# atsams70n-switch.net
KiCad netlist of a schematic drawn in EAGLE
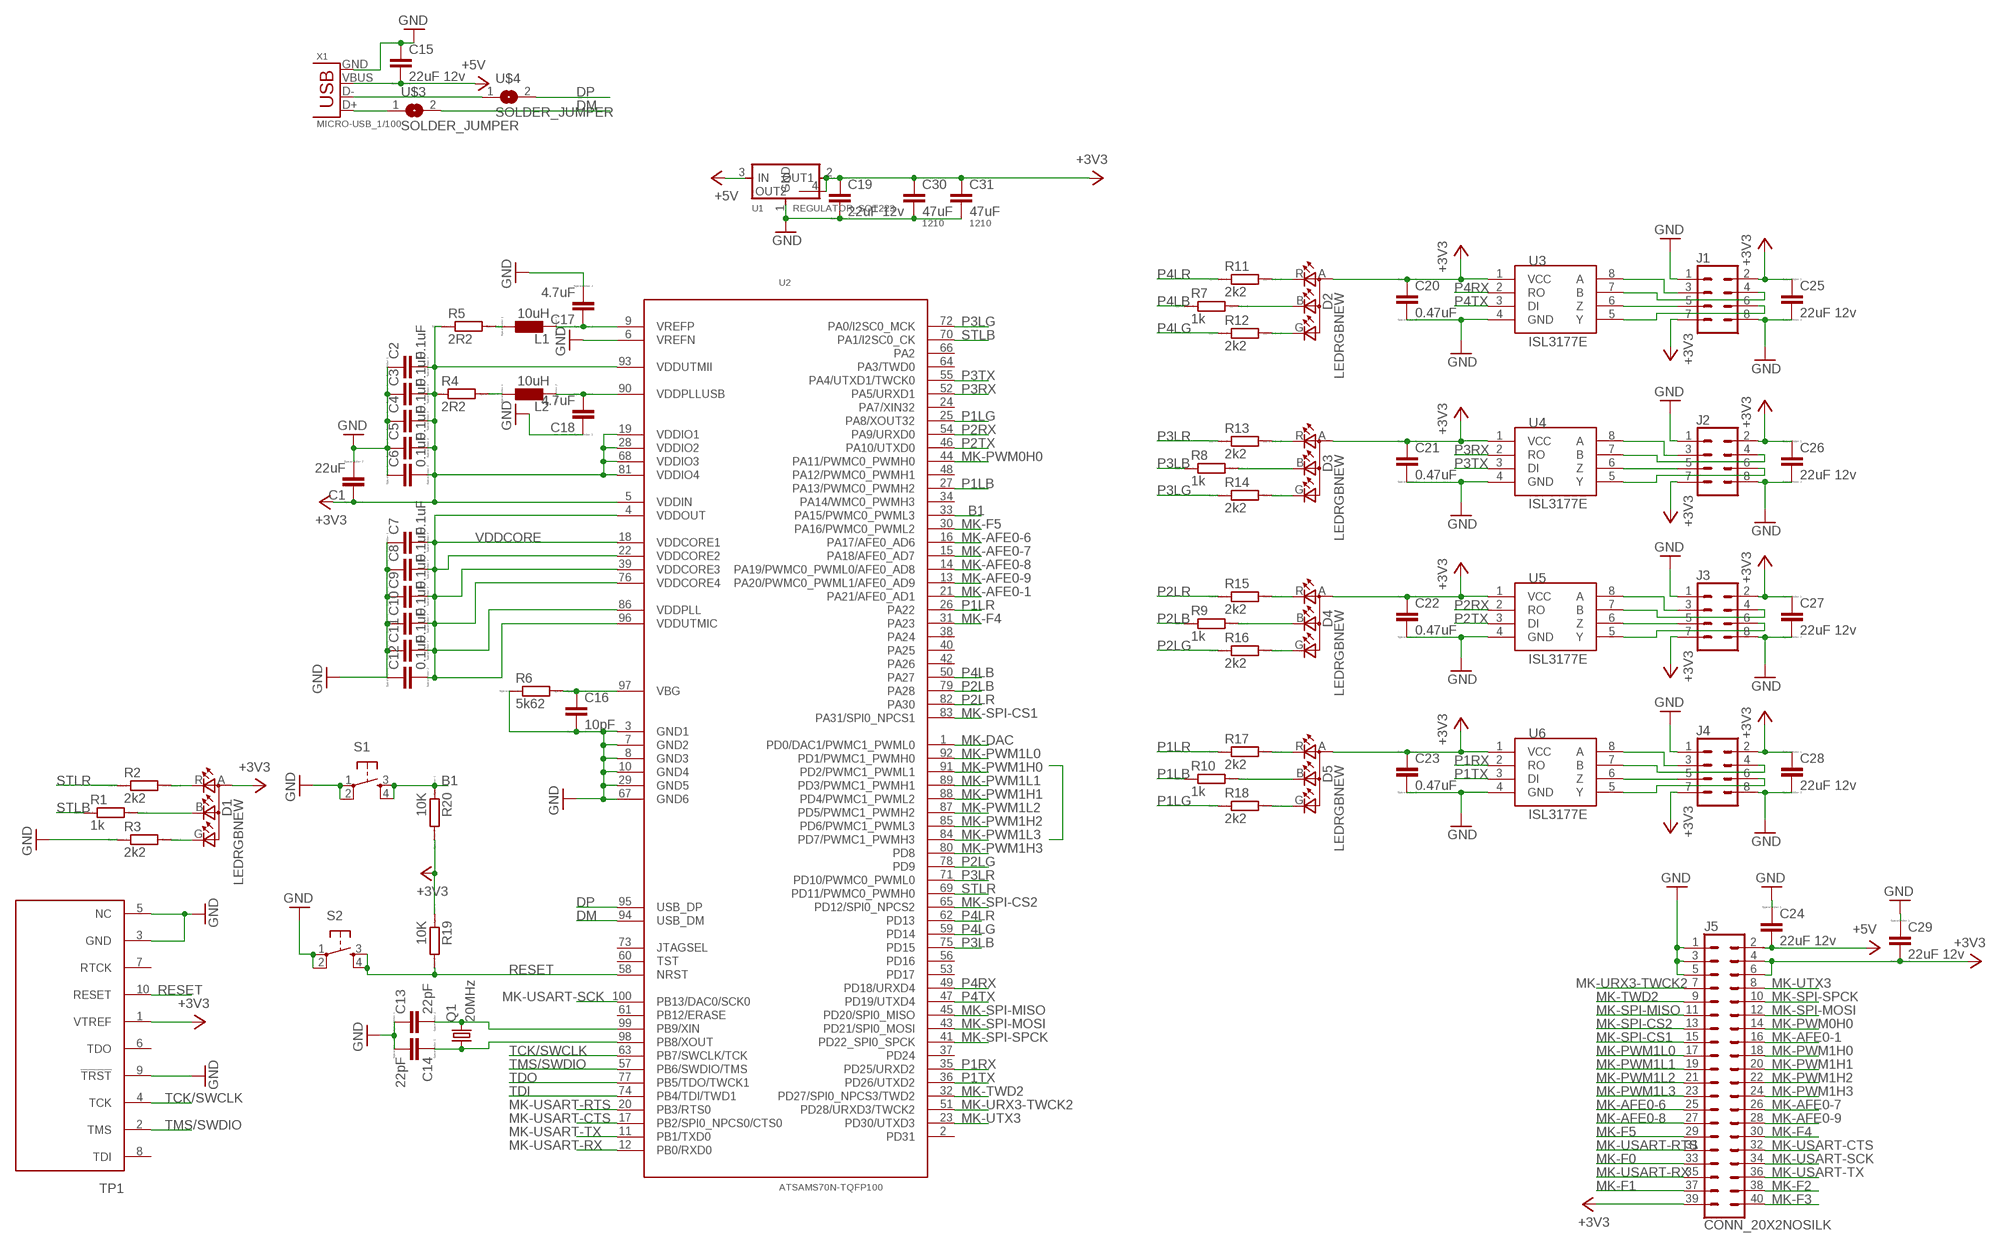
[diagram p0: schematic, sheet 1]

(export (version "E")
  (design (tool "Eeschema 10.0.6"))
  (components
    (comp (ref "C1")
      (value "22uF")
      (footprint "eagle-import:C0805")
      (libsource (lib "eagle-import") (part "C"))
    )
    (comp (ref "C2")
      (value "0.1uF")
      (footprint "eagle-import:C0603")
      (libsource (lib "eagle-import") (part "CC0603"))
    )
    (comp (ref "C3")
      (value "0.1uF")
      (footprint "eagle-import:C0603")
      (libsource (lib "eagle-import") (part "CC0603"))
    )
    (comp (ref "C4")
      (value "0.1uF")
      (footprint "eagle-import:C0603")
      (libsource (lib "eagle-import") (part "CC0603"))
    )
    (comp (ref "C5")
      (value "0.1uF")
      (footprint "eagle-import:C0603")
      (libsource (lib "eagle-import") (part "CC0603"))
    )
    (comp (ref "C6")
      (value "0.1uF")
      (footprint "eagle-import:C0603")
      (libsource (lib "eagle-import") (part "CC0603"))
    )
    (comp (ref "C7")
      (value "0.1uF")
      (footprint "eagle-import:C0603")
      (libsource (lib "eagle-import") (part "CC0603"))
    )
    (comp (ref "C8")
      (value "0.1uF")
      (footprint "eagle-import:C0603")
      (libsource (lib "eagle-import") (part "CC0603"))
    )
    (comp (ref "C9")
      (value "0.1uF")
      (footprint "eagle-import:C0603")
      (libsource (lib "eagle-import") (part "CC0603"))
    )
    (comp (ref "C10")
      (value "0.1uF")
      (footprint "eagle-import:C0603")
      (libsource (lib "eagle-import") (part "CC0603"))
    )
    (comp (ref "C11")
      (value "0.1uF")
      (footprint "eagle-import:C0603")
      (libsource (lib "eagle-import") (part "CC0603"))
    )
    (comp (ref "C12")
      (value "0.1uF")
      (footprint "eagle-import:C0603")
      (libsource (lib "eagle-import") (part "CC0603"))
    )
    (comp (ref "C13")
      (value "22pF")
      (footprint "eagle-import:C0603")
      (libsource (lib "eagle-import") (part "CC0603"))
    )
    (comp (ref "C14")
      (value "22pF")
      (footprint "eagle-import:C0603")
      (libsource (lib "eagle-import") (part "CC0603"))
    )
    (comp (ref "C15")
      (value "22uF 12v")
      (footprint "eagle-import:C0805")
      (libsource (lib "eagle-import") (part "C"))
    )
    (comp (ref "C16")
      (value "10pF")
      (footprint "eagle-import:C0805")
      (libsource (lib "eagle-import") (part "C"))
    )
    (comp (ref "C17")
      (value "4.7uF")
      (footprint "eagle-import:C0805")
      (libsource (lib "eagle-import") (part "C"))
    )
    (comp (ref "C18")
      (value "4.7uF")
      (footprint "eagle-import:C0805")
      (libsource (lib "eagle-import") (part "C"))
    )
    (comp (ref "C19")
      (value "22uF 12v")
      (footprint "eagle-import:C0805")
      (libsource (lib "eagle-import") (part "C"))
    )
    (comp (ref "C20")
      (value "0.47uF")
      (footprint "eagle-import:C0805")
      (libsource (lib "eagle-import") (part "C"))
    )
    (comp (ref "C21")
      (value "0.47uF")
      (footprint "eagle-import:C0805")
      (libsource (lib "eagle-import") (part "C"))
    )
    (comp (ref "C22")
      (value "0.47uF")
      (footprint "eagle-import:C0805")
      (libsource (lib "eagle-import") (part "C"))
    )
    (comp (ref "C23")
      (value "0.47uF")
      (footprint "eagle-import:C0805")
      (libsource (lib "eagle-import") (part "C"))
    )
    (comp (ref "C24")
      (value "22uF 12v")
      (footprint "eagle-import:C0805")
      (libsource (lib "eagle-import") (part "C"))
    )
    (comp (ref "C25")
      (value "22uF 12v")
      (footprint "eagle-import:C0805")
      (libsource (lib "eagle-import") (part "C"))
    )
    (comp (ref "C26")
      (value "22uF 12v")
      (footprint "eagle-import:C0805")
      (libsource (lib "eagle-import") (part "C"))
    )
    (comp (ref "C27")
      (value "22uF 12v")
      (footprint "eagle-import:C0805")
      (libsource (lib "eagle-import") (part "C"))
    )
    (comp (ref "C28")
      (value "22uF 12v")
      (footprint "eagle-import:C0805")
      (libsource (lib "eagle-import") (part "C"))
    )
    (comp (ref "C29")
      (value "22uF 12v")
      (footprint "eagle-import:C0805")
      (libsource (lib "eagle-import") (part "C"))
    )
    (comp (ref "C30")
      (value "47uF")
      (footprint "eagle-import:1210")
      (libsource (lib "eagle-import") (part "CAP1210"))
    )
    (comp (ref "C31")
      (value "47uF")
      (footprint "eagle-import:1210")
      (libsource (lib "eagle-import") (part "CAP1210"))
    )
    (comp (ref "D1")
      (value "LEDRGBNEW")
      (footprint "eagle-import:P-LCC-4")
      (libsource (lib "eagle-import") (part "LEDRGBNEW"))
    )
    (comp (ref "D2")
      (value "LEDRGBNEW")
      (footprint "eagle-import:P-LCC-4")
      (libsource (lib "eagle-import") (part "LEDRGBNEW"))
    )
    (comp (ref "D3")
      (value "LEDRGBNEW")
      (footprint "eagle-import:P-LCC-4")
      (libsource (lib "eagle-import") (part "LEDRGBNEW"))
    )
    (comp (ref "D4")
      (value "LEDRGBNEW")
      (footprint "eagle-import:P-LCC-4")
      (libsource (lib "eagle-import") (part "LEDRGBNEW"))
    )
    (comp (ref "D5")
      (value "LEDRGBNEW")
      (footprint "eagle-import:P-LCC-4")
      (libsource (lib "eagle-import") (part "LEDRGBNEW"))
    )
    (comp (ref "J1")
      (value "CONN_04X2SHROUDED")
      (footprint "eagle-import:2X4-SHROUDED")
      (libsource (lib "eagle-import") (part "CONN_04X2SHROUDED"))
    )
    (comp (ref "J2")
      (value "CONN_04X2SHROUDED")
      (footprint "eagle-import:2X4-SHROUDED")
      (libsource (lib "eagle-import") (part "CONN_04X2SHROUDED"))
    )
    (comp (ref "J3")
      (value "CONN_04X2SHROUDED")
      (footprint "eagle-import:2X4-SHROUDED")
      (libsource (lib "eagle-import") (part "CONN_04X2SHROUDED"))
    )
    (comp (ref "J4")
      (value "CONN_04X2SHROUDED")
      (footprint "eagle-import:2X4-SHROUDED")
      (libsource (lib "eagle-import") (part "CONN_04X2SHROUDED"))
    )
    (comp (ref "J5")
      (value "CONN_20X2NOSILK")
      (footprint "eagle-import:2X20_NOSILK")
      (libsource (lib "eagle-import") (part "CONN_20X2NOSILK"))
    )
    (comp (ref "L1")
      (value "10uH")
      (footprint "eagle-import:L1812")
      (libsource (lib "eagle-import") (part "L"))
    )
    (comp (ref "L2")
      (value "10uH")
      (footprint "eagle-import:L1812")
      (libsource (lib "eagle-import") (part "L"))
    )
    (comp (ref "Q1")
      (value "20MHz")
      (footprint "eagle-import:CTS406")
      (libsource (lib "eagle-import") (part "CRYSTALCTS406"))
    )
    (comp (ref "R1")
      (value "1k")
      (footprint "eagle-import:R0805")
      (libsource (lib "eagle-import") (part "R"))
    )
    (comp (ref "R2")
      (value "2k2")
      (footprint "eagle-import:R0805")
      (libsource (lib "eagle-import") (part "R"))
    )
    (comp (ref "R3")
      (value "2k2")
      (footprint "eagle-import:R0805")
      (libsource (lib "eagle-import") (part "R"))
    )
    (comp (ref "R4")
      (value "2R2")
      (footprint "eagle-import:R0805")
      (libsource (lib "eagle-import") (part "R"))
    )
    (comp (ref "R5")
      (value "2R2")
      (footprint "eagle-import:R0805")
      (libsource (lib "eagle-import") (part "R"))
    )
    (comp (ref "R6")
      (value "5k62")
      (footprint "eagle-import:R0805")
      (libsource (lib "eagle-import") (part "R"))
    )
    (comp (ref "R7")
      (value "1k")
      (footprint "eagle-import:R0805")
      (libsource (lib "eagle-import") (part "R"))
    )
    (comp (ref "R8")
      (value "1k")
      (footprint "eagle-import:R0805")
      (libsource (lib "eagle-import") (part "R"))
    )
    (comp (ref "R9")
      (value "1k")
      (footprint "eagle-import:R0805")
      (libsource (lib "eagle-import") (part "R"))
    )
    (comp (ref "R10")
      (value "1k")
      (footprint "eagle-import:R0805")
      (libsource (lib "eagle-import") (part "R"))
    )
    (comp (ref "R11")
      (value "2k2")
      (footprint "eagle-import:R0805")
      (libsource (lib "eagle-import") (part "R"))
    )
    (comp (ref "R12")
      (value "2k2")
      (footprint "eagle-import:R0805")
      (libsource (lib "eagle-import") (part "R"))
    )
    (comp (ref "R13")
      (value "2k2")
      (footprint "eagle-import:R0805")
      (libsource (lib "eagle-import") (part "R"))
    )
    (comp (ref "R14")
      (value "2k2")
      (footprint "eagle-import:R0805")
      (libsource (lib "eagle-import") (part "R"))
    )
    (comp (ref "R15")
      (value "2k2")
      (footprint "eagle-import:R0805")
      (libsource (lib "eagle-import") (part "R"))
    )
    (comp (ref "R16")
      (value "2k2")
      (footprint "eagle-import:R0805")
      (libsource (lib "eagle-import") (part "R"))
    )
    (comp (ref "R17")
      (value "2k2")
      (footprint "eagle-import:R0805")
      (libsource (lib "eagle-import") (part "R"))
    )
    (comp (ref "R18")
      (value "2k2")
      (footprint "eagle-import:R0805")
      (libsource (lib "eagle-import") (part "R"))
    )
    (comp (ref "R19")
      (value "10K")
      (footprint "eagle-import:R0805")
      (libsource (lib "eagle-import") (part "R"))
    )
    (comp (ref "R20")
      (value "10K")
      (footprint "eagle-import:R0805")
      (libsource (lib "eagle-import") (part "R"))
    )
    (comp (ref "S1")
      (value "6MM_SWITCH6MM_SWITCH")
      (footprint "eagle-import:6MM_SWITCH")
      (libsource (lib "eagle-import") (part "6MM_SWITCH6MM_SWITCH"))
    )
    (comp (ref "S2")
      (value "6MM_SWITCH6MM_SWITCH")
      (footprint "eagle-import:6MM_SWITCH")
      (libsource (lib "eagle-import") (part "6MM_SWITCH6MM_SWITCH"))
    )
    (comp (ref "TP1")
      (value "TC2050-NL")
      (footprint "eagle-import:TC2050-MCP")
      (libsource (lib "eagle-import") (part "TC2050-NL"))
    )
    (comp (ref "U$3")
      (value "SOLDER_JUMPER")
      (footprint "eagle-import:SJFAB")
      (libsource (lib "eagle-import") (part "SOLDER_JUMPER"))
    )
    (comp (ref "U$4")
      (value "SOLDER_JUMPER")
      (footprint "eagle-import:SJFAB")
      (libsource (lib "eagle-import") (part "SOLDER_JUMPER"))
    )
    (comp (ref "U1")
      (value "REGULATOR_SOT223")
      (footprint "eagle-import:SOT223")
      (libsource (lib "eagle-import") (part "REGULATOR_SOT223"))
    )
    (comp (ref "U2")
      (value "ATSAMS70N-TQFP100")
      (footprint "eagle-import:TQFP100-14X14")
      (libsource (lib "eagle-import") (part "ATSAMS70N-TQFP100"))
    )
    (comp (ref "U3")
      (value "ISL3177E")
      (footprint "eagle-import:MSOP8")
      (libsource (lib "eagle-import") (part "ISL3177E"))
    )
    (comp (ref "U4")
      (value "ISL3177E")
      (footprint "eagle-import:MSOP8")
      (libsource (lib "eagle-import") (part "ISL3177E"))
    )
    (comp (ref "U5")
      (value "ISL3177E")
      (footprint "eagle-import:MSOP8")
      (libsource (lib "eagle-import") (part "ISL3177E"))
    )
    (comp (ref "U6")
      (value "ISL3177E")
      (footprint "eagle-import:MSOP8")
      (libsource (lib "eagle-import") (part "ISL3177E"))
    )
    (comp (ref "X1")
      (value "MICRO-USB_1/100")
      (footprint "eagle-import:DX4R005HJ5_100")
      (libsource (lib "eagle-import") (part "MICRO-USB_1/100"))
    )
  )
  (nets
    (net (code "1") (name "+3V3") (class "Default")
      (node (ref "C1") (pin "1") (pinfunction "1_1") (pintype "passive"))
      (node (ref "C19") (pin "1") (pinfunction "1_1") (pintype "passive"))
      (node (ref "C2") (pin "2") (pinfunction "2_2") (pintype "passive"))
      (node (ref "C20") (pin "1") (pinfunction "1_1") (pintype "passive"))
      (node (ref "C21") (pin "1") (pinfunction "1_1") (pintype "passive"))
      (node (ref "C22") (pin "1") (pinfunction "1_1") (pintype "passive"))
      (node (ref "C23") (pin "1") (pinfunction "1_1") (pintype "passive"))
      (node (ref "C25") (pin "1") (pinfunction "1_1") (pintype "passive"))
      (node (ref "C26") (pin "1") (pinfunction "1_1") (pintype "passive"))
      (node (ref "C27") (pin "1") (pinfunction "1_1") (pintype "passive"))
      (node (ref "C28") (pin "1") (pinfunction "1_1") (pintype "passive"))
      (node (ref "C29") (pin "2") (pinfunction "2_2") (pintype "passive"))
      (node (ref "C3") (pin "2") (pinfunction "2_2") (pintype "passive"))
      (node (ref "C30") (pin "1") (pinfunction "1_1") (pintype "passive"))
      (node (ref "C31") (pin "1") (pinfunction "1_1") (pintype "passive"))
      (node (ref "C4") (pin "2") (pinfunction "2_2") (pintype "passive"))
      (node (ref "C5") (pin "2") (pinfunction "2_2") (pintype "passive"))
      (node (ref "C6") (pin "2") (pinfunction "2_2") (pintype "passive"))
      (node (ref "D1") (pin "A") (pinfunction "A2_A") (pintype "passive"))
      (node (ref "D2") (pin "A") (pinfunction "A2_A") (pintype "passive"))
      (node (ref "D3") (pin "A") (pinfunction "A2_A") (pintype "passive"))
      (node (ref "D4") (pin "A") (pinfunction "A2_A") (pintype "passive"))
      (node (ref "D5") (pin "A") (pinfunction "A2_A") (pintype "passive"))
      (node (ref "J1") (pin "2") (pinfunction "2_2") (pintype "passive"))
      (node (ref "J1") (pin "7") (pinfunction "7_7") (pintype "passive"))
      (node (ref "J2") (pin "2") (pinfunction "2_2") (pintype "passive"))
      (node (ref "J2") (pin "7") (pinfunction "7_7") (pintype "passive"))
      (node (ref "J3") (pin "2") (pinfunction "2_2") (pintype "passive"))
      (node (ref "J3") (pin "7") (pinfunction "7_7") (pintype "passive"))
      (node (ref "J4") (pin "2") (pinfunction "2_2") (pintype "passive"))
      (node (ref "J4") (pin "7") (pinfunction "7_7") (pintype "passive"))
      (node (ref "J5") (pin "39") (pinfunction "39_39") (pintype "passive"))
      (node (ref "J5") (pin "4") (pinfunction "4_4") (pintype "passive"))
      (node (ref "J5") (pin "6") (pinfunction "6_6") (pintype "passive"))
      (node (ref "R19") (pin "1") (pinfunction "1_1") (pintype "passive"))
      (node (ref "R20") (pin "2") (pinfunction "2_2") (pintype "passive"))
      (node (ref "R4") (pin "1") (pinfunction "1_1") (pintype "passive"))
      (node (ref "R5") (pin "1") (pinfunction "1_1") (pintype "passive"))
      (node (ref "TP1") (pin "1") (pinfunction "VTREF_1") (pintype "bidirectional"))
      (node (ref "U1") (pin "2") (pinfunction "OUT1_2") (pintype "bidirectional"))
      (node (ref "U1") (pin "4") (pinfunction "OUT2_4") (pintype "bidirectional"))
      (node (ref "U2") (pin "19") (pinfunction "VDDIO1_19") (pintype "bidirectional"))
      (node (ref "U2") (pin "28") (pinfunction "VDDIO2_28") (pintype "bidirectional"))
      (node (ref "U2") (pin "5") (pinfunction "VDDIN_5") (pintype "bidirectional"))
      (node (ref "U2") (pin "68") (pinfunction "VDDIO3_68") (pintype "bidirectional"))
      (node (ref "U2") (pin "81") (pinfunction "VDDIO4_81") (pintype "bidirectional"))
      (node (ref "U2") (pin "93") (pinfunction "VDDUTMII_93") (pintype "bidirectional"))
      (node (ref "U3") (pin "1") (pinfunction "VCC_1") (pintype "bidirectional"))
      (node (ref "U4") (pin "1") (pinfunction "VCC_1") (pintype "bidirectional"))
      (node (ref "U5") (pin "1") (pinfunction "VCC_1") (pintype "bidirectional"))
      (node (ref "U6") (pin "1") (pinfunction "VCC_1") (pintype "bidirectional"))
    )
    (net (code "2") (name "+5V") (class "Default")
      (node (ref "C15") (pin "2") (pinfunction "2_2") (pintype "passive"))
      (node (ref "C24") (pin "2") (pinfunction "2_2") (pintype "passive"))
      (node (ref "J5") (pin "2") (pinfunction "2_2") (pintype "passive"))
      (node (ref "U1") (pin "3") (pinfunction "IN_3") (pintype "bidirectional"))
      (node (ref "X1") (pin "VBUS") (pinfunction "VBUS_VBUS") (pintype "bidirectional"))
    )
    (net (code "3") (name "/B1") (class "Default")
      (node (ref "R20") (pin "1") (pinfunction "1_1") (pintype "passive"))
      (node (ref "S1") (pin "3") (pinfunction "S_3") (pintype "passive"))
      (node (ref "S1") (pin "4") (pinfunction "S1_4") (pintype "passive"))
      (node (ref "U2") (pin "33") (pinfunction "PA15/PWMC0_PWML3_33") (pintype "bidirectional"))
    )
    (net (code "4") (name "/DM") (class "Default")
      (node (ref "U$3") (pin "2") (pinfunction "2_2") (pintype "passive"))
      (node (ref "U2") (pin "94") (pinfunction "USB_DM_94") (pintype "bidirectional"))
    )
    (net (code "5") (name "/DP") (class "Default")
      (node (ref "U$4") (pin "2") (pinfunction "2_2") (pintype "passive"))
      (node (ref "U2") (pin "95") (pinfunction "USB_DP_95") (pintype "bidirectional"))
    )
    (net (code "6") (name "/MK-AFE0-1") (class "Default")
      (node (ref "J5") (pin "16") (pinfunction "16_16") (pintype "passive"))
      (node (ref "U2") (pin "21") (pinfunction "PA21/AFE0_AD1_21") (pintype "bidirectional"))
    )
    (net (code "7") (name "/MK-AFE0-6") (class "Default")
      (node (ref "J5") (pin "25") (pinfunction "25_25") (pintype "passive"))
      (node (ref "U2") (pin "16") (pinfunction "PA17/AFE0_AD6_16") (pintype "bidirectional"))
    )
    (net (code "8") (name "/MK-AFE0-7") (class "Default")
      (node (ref "J5") (pin "26") (pinfunction "26_26") (pintype "passive"))
      (node (ref "U2") (pin "15") (pinfunction "PA18/AFE0_AD7_15") (pintype "bidirectional"))
    )
    (net (code "9") (name "/MK-AFE0-8") (class "Default")
      (node (ref "J5") (pin "27") (pinfunction "27_27") (pintype "passive"))
      (node (ref "U2") (pin "14") (pinfunction "PA19/PWMC0_PWML0/AFE0_AD8_14") (pintype "bidirectional"))
    )
    (net (code "10") (name "/MK-AFE0-9") (class "Default")
      (node (ref "J5") (pin "28") (pinfunction "28_28") (pintype "passive"))
      (node (ref "U2") (pin "13") (pinfunction "PA20/PWMC0_PWML1/AFE0_AD9_13") (pintype "bidirectional"))
    )
    (net (code "11") (name "/MK-DAC") (class "Default")
      (node (ref "U2") (pin "1") (pinfunction "PD0/DAC1/PWMC1_PWML0_1") (pintype "bidirectional"))
    )
    (net (code "12") (name "/MK-F0") (class "Default")
      (node (ref "J5") (pin "33") (pinfunction "33_33") (pintype "passive"))
    )
    (net (code "13") (name "/MK-F1") (class "Default")
      (node (ref "J5") (pin "37") (pinfunction "37_37") (pintype "passive"))
    )
    (net (code "14") (name "/MK-F2") (class "Default")
      (node (ref "J5") (pin "38") (pinfunction "38_38") (pintype "passive"))
    )
    (net (code "15") (name "/MK-F3") (class "Default")
      (node (ref "J5") (pin "40") (pinfunction "40_40") (pintype "passive"))
    )
    (net (code "16") (name "/MK-F4") (class "Default")
      (node (ref "J5") (pin "30") (pinfunction "30_30") (pintype "passive"))
      (node (ref "U2") (pin "31") (pinfunction "PA23_31") (pintype "bidirectional"))
    )
    (net (code "17") (name "/MK-F5") (class "Default")
      (node (ref "J5") (pin "29") (pinfunction "29_29") (pintype "passive"))
      (node (ref "U2") (pin "30") (pinfunction "PA16/PWMC0_PWML2_30") (pintype "bidirectional"))
    )
    (net (code "18") (name "/MK-PWM0H0") (class "Default")
      (node (ref "J5") (pin "14") (pinfunction "14_14") (pintype "passive"))
      (node (ref "U2") (pin "44") (pinfunction "PA11/PWMC0_PWMH0_44") (pintype "bidirectional"))
    )
    (net (code "19") (name "/MK-PWM1H0") (class "Default")
      (node (ref "J5") (pin "18") (pinfunction "18_18") (pintype "passive"))
      (node (ref "U2") (pin "91") (pinfunction "PD2/PWMC1_PWML1_91") (pintype "bidirectional"))
    )
    (net (code "20") (name "/MK-PWM1H1") (class "Default")
      (node (ref "J5") (pin "20") (pinfunction "20_20") (pintype "passive"))
      (node (ref "U2") (pin "88") (pinfunction "PD4/PWMC1_PWML2_88") (pintype "bidirectional"))
    )
    (net (code "21") (name "/MK-PWM1H2") (class "Default")
      (node (ref "J5") (pin "22") (pinfunction "22_22") (pintype "passive"))
      (node (ref "U2") (pin "85") (pinfunction "PD6/PWMC1_PWML3_85") (pintype "bidirectional"))
    )
    (net (code "22") (name "/MK-PWM1H3") (class "Default")
      (node (ref "J5") (pin "24") (pinfunction "24_24") (pintype "passive"))
      (node (ref "U2") (pin "80") (pinfunction "PD8_80") (pintype "bidirectional"))
    )
    (net (code "23") (name "/MK-PWM1L0") (class "Default")
      (node (ref "J5") (pin "17") (pinfunction "17_17") (pintype "passive"))
      (node (ref "U2") (pin "92") (pinfunction "PD1/PWMC1_PWMH0_92") (pintype "bidirectional"))
    )
    (net (code "24") (name "/MK-PWM1L1") (class "Default")
      (node (ref "J5") (pin "19") (pinfunction "19_19") (pintype "passive"))
      (node (ref "U2") (pin "89") (pinfunction "PD3/PWMC1_PWMH1_89") (pintype "bidirectional"))
    )
    (net (code "25") (name "/MK-PWM1L2") (class "Default")
      (node (ref "J5") (pin "21") (pinfunction "21_21") (pintype "passive"))
      (node (ref "U2") (pin "87") (pinfunction "PD5/PWMC1_PWMH2_87") (pintype "bidirectional"))
    )
    (net (code "26") (name "/MK-PWM1L3") (class "Default")
      (node (ref "J5") (pin "23") (pinfunction "23_23") (pintype "passive"))
      (node (ref "U2") (pin "84") (pinfunction "PD7/PWMC1_PWMH3_84") (pintype "bidirectional"))
    )
    (net (code "27") (name "/MK-SPI-CS1") (class "Default")
      (node (ref "J5") (pin "15") (pinfunction "15_15") (pintype "passive"))
      (node (ref "U2") (pin "83") (pinfunction "PA31/SPI0_NPCS1_83") (pintype "bidirectional"))
    )
    (net (code "28") (name "/MK-SPI-CS2") (class "Default")
      (node (ref "J5") (pin "13") (pinfunction "13_13") (pintype "passive"))
      (node (ref "U2") (pin "65") (pinfunction "PD12/SPI0_NPCS2_65") (pintype "bidirectional"))
    )
    (net (code "29") (name "/MK-SPI-MISO") (class "Default")
      (node (ref "J5") (pin "11") (pinfunction "11_11") (pintype "passive"))
      (node (ref "U2") (pin "45") (pinfunction "PD20/SPI0_MISO_45") (pintype "bidirectional"))
    )
    (net (code "30") (name "/MK-SPI-MOSI") (class "Default")
      (node (ref "J5") (pin "12") (pinfunction "12_12") (pintype "passive"))
      (node (ref "U2") (pin "43") (pinfunction "PD21/SPI0_MOSI_43") (pintype "bidirectional"))
    )
    (net (code "31") (name "/MK-SPI-SPCK") (class "Default")
      (node (ref "J5") (pin "10") (pinfunction "10_10") (pintype "passive"))
      (node (ref "U2") (pin "41") (pinfunction "PD22_SPI0_SPCK_41") (pintype "bidirectional"))
    )
    (net (code "32") (name "/MK-TWD2") (class "Default")
      (node (ref "J5") (pin "9") (pinfunction "9_9") (pintype "passive"))
      (node (ref "U2") (pin "32") (pinfunction "PD27/SPI0_NPCS3/TWD2_32") (pintype "bidirectional"))
    )
    (net (code "33") (name "/MK-URX3-TWCK2") (class "Default")
      (node (ref "J5") (pin "7") (pinfunction "7_7") (pintype "passive"))
      (node (ref "U2") (pin "51") (pinfunction "PD28/URXD3/TWCK2_51") (pintype "bidirectional"))
    )
    (net (code "34") (name "/MK-USART-CTS") (class "Default")
      (node (ref "J5") (pin "32") (pinfunction "32_32") (pintype "passive"))
      (node (ref "U2") (pin "17") (pinfunction "PB2/SPI0_NPCS0/CTS0_17") (pintype "bidirectional"))
    )
    (net (code "35") (name "/MK-USART-RTS") (class "Default")
      (node (ref "J5") (pin "31") (pinfunction "31_31") (pintype "passive"))
      (node (ref "U2") (pin "20") (pinfunction "PB3/RTS0_20") (pintype "bidirectional"))
    )
    (net (code "36") (name "/MK-USART-RX") (class "Default")
      (node (ref "J5") (pin "35") (pinfunction "35_35") (pintype "passive"))
      (node (ref "U2") (pin "12") (pinfunction "PB0/RXD0_12") (pintype "bidirectional"))
    )
    (net (code "37") (name "/MK-USART-SCK") (class "Default")
      (node (ref "J5") (pin "34") (pinfunction "34_34") (pintype "passive"))
      (node (ref "U2") (pin "100") (pinfunction "PB13/DAC0/SCK0_100") (pintype "bidirectional"))
    )
    (net (code "38") (name "/MK-USART-TX") (class "Default")
      (node (ref "J5") (pin "36") (pinfunction "36_36") (pintype "passive"))
      (node (ref "U2") (pin "11") (pinfunction "PB1/TXD0_11") (pintype "bidirectional"))
    )
    (net (code "39") (name "/MK-UTX3") (class "Default")
      (node (ref "J5") (pin "8") (pinfunction "8_8") (pintype "passive"))
      (node (ref "U2") (pin "23") (pinfunction "PD30/UTXD3_23") (pintype "bidirectional"))
    )
    (net (code "40") (name "/P1LB") (class "Default")
      (node (ref "R10") (pin "1") (pinfunction "1_1") (pintype "passive"))
      (node (ref "U2") (pin "27") (pinfunction "PA13/PWMC0_PWMH2_27") (pintype "bidirectional"))
    )
    (net (code "41") (name "/P1LG") (class "Default")
      (node (ref "R18") (pin "1") (pinfunction "1_1") (pintype "passive"))
      (node (ref "U2") (pin "25") (pinfunction "PA8/XOUT32_25") (pintype "bidirectional"))
    )
    (net (code "42") (name "/P1LR") (class "Default")
      (node (ref "R17") (pin "1") (pinfunction "1_1") (pintype "passive"))
      (node (ref "U2") (pin "26") (pinfunction "PA22_26") (pintype "bidirectional"))
    )
    (net (code "43") (name "/P1RX") (class "Default")
      (node (ref "U2") (pin "35") (pinfunction "PD25/URXD2_35") (pintype "bidirectional"))
      (node (ref "U6") (pin "2") (pinfunction "RO_2") (pintype "bidirectional"))
    )
    (net (code "44") (name "/P1TX") (class "Default")
      (node (ref "U2") (pin "36") (pinfunction "PD26/UTXD2_36") (pintype "bidirectional"))
      (node (ref "U6") (pin "3") (pinfunction "DI_3") (pintype "bidirectional"))
    )
    (net (code "45") (name "/P2LB") (class "Default")
      (node (ref "R9") (pin "1") (pinfunction "1_1") (pintype "passive"))
      (node (ref "U2") (pin "79") (pinfunction "PA28_79") (pintype "bidirectional"))
    )
    (net (code "46") (name "/P2LG") (class "Default")
      (node (ref "R16") (pin "1") (pinfunction "1_1") (pintype "passive"))
      (node (ref "U2") (pin "78") (pinfunction "PD9_78") (pintype "bidirectional"))
    )
    (net (code "47") (name "/P2LR") (class "Default")
      (node (ref "R15") (pin "1") (pinfunction "1_1") (pintype "passive"))
      (node (ref "U2") (pin "82") (pinfunction "PA30_82") (pintype "bidirectional"))
    )
    (net (code "48") (name "/P2RX") (class "Default")
      (node (ref "U2") (pin "54") (pinfunction "PA9/URXD0_54") (pintype "bidirectional"))
      (node (ref "U5") (pin "2") (pinfunction "RO_2") (pintype "bidirectional"))
    )
    (net (code "49") (name "/P2TX") (class "Default")
      (node (ref "U2") (pin "46") (pinfunction "PA10/UTXD0_46") (pintype "bidirectional"))
      (node (ref "U5") (pin "3") (pinfunction "DI_3") (pintype "bidirectional"))
    )
    (net (code "50") (name "/P3LB") (class "Default")
      (node (ref "R8") (pin "1") (pinfunction "1_1") (pintype "passive"))
      (node (ref "U2") (pin "75") (pinfunction "PD15_75") (pintype "bidirectional"))
    )
    (net (code "51") (name "/P3LG") (class "Default")
      (node (ref "R14") (pin "1") (pinfunction "1_1") (pintype "passive"))
      (node (ref "U2") (pin "72") (pinfunction "PA0/I2SC0_MCK_72") (pintype "bidirectional"))
    )
    (net (code "52") (name "/P3LR") (class "Default")
      (node (ref "R13") (pin "1") (pinfunction "1_1") (pintype "passive"))
      (node (ref "U2") (pin "71") (pinfunction "PD10/PWMC0_PWML0_71") (pintype "bidirectional"))
    )
    (net (code "53") (name "/P3RX") (class "Default")
      (node (ref "U2") (pin "52") (pinfunction "PA5/URXD1_52") (pintype "bidirectional"))
      (node (ref "U4") (pin "2") (pinfunction "RO_2") (pintype "bidirectional"))
    )
    (net (code "54") (name "/P3TX") (class "Default")
      (node (ref "U2") (pin "55") (pinfunction "PA4/UTXD1/TWCK0_55") (pintype "bidirectional"))
      (node (ref "U4") (pin "3") (pinfunction "DI_3") (pintype "bidirectional"))
    )
    (net (code "55") (name "/P4LB") (class "Default")
      (node (ref "R7") (pin "1") (pinfunction "1_1") (pintype "passive"))
      (node (ref "U2") (pin "50") (pinfunction "PA27_50") (pintype "bidirectional"))
    )
    (net (code "56") (name "/P4LG") (class "Default")
      (node (ref "R12") (pin "1") (pinfunction "1_1") (pintype "passive"))
      (node (ref "U2") (pin "59") (pinfunction "PD14_59") (pintype "bidirectional"))
    )
    (net (code "57") (name "/P4LR") (class "Default")
      (node (ref "R11") (pin "1") (pinfunction "1_1") (pintype "passive"))
      (node (ref "U2") (pin "62") (pinfunction "PD13_62") (pintype "bidirectional"))
    )
    (net (code "58") (name "/P4RX") (class "Default")
      (node (ref "U2") (pin "49") (pinfunction "PD18/URXD4_49") (pintype "bidirectional"))
      (node (ref "U3") (pin "2") (pinfunction "RO_2") (pintype "bidirectional"))
    )
    (net (code "59") (name "/P4TX") (class "Default")
      (node (ref "U2") (pin "47") (pinfunction "PD19/UTXD4_47") (pintype "bidirectional"))
      (node (ref "U3") (pin "3") (pinfunction "DI_3") (pintype "bidirectional"))
    )
    (net (code "60") (name "/RESET") (class "Default")
      (node (ref "R19") (pin "2") (pinfunction "2_2") (pintype "passive"))
      (node (ref "S2") (pin "3") (pinfunction "S_3") (pintype "passive"))
      (node (ref "S2") (pin "4") (pinfunction "S1_4") (pintype "passive"))
      (node (ref "TP1") (pin "10") (pinfunction "RESET_10") (pintype "bidirectional"))
      (node (ref "U2") (pin "58") (pinfunction "NRST_58") (pintype "bidirectional"))
    )
    (net (code "61") (name "/STLB") (class "Default")
      (node (ref "R1") (pin "1") (pinfunction "1_1") (pintype "passive"))
      (node (ref "U2") (pin "70") (pinfunction "PA1/I2SC0_CK_70") (pintype "bidirectional"))
    )
    (net (code "62") (name "/STLR") (class "Default")
      (node (ref "R2") (pin "1") (pinfunction "1_1") (pintype "passive"))
      (node (ref "U2") (pin "69") (pinfunction "PD11/PWMC0_PWMH0_69") (pintype "bidirectional"))
    )
    (net (code "63") (name "/TCK{slash}SWCLK") (class "Default")
      (node (ref "TP1") (pin "4") (pinfunction "TCK_4") (pintype "bidirectional"))
      (node (ref "U2") (pin "63") (pinfunction "PB7/SWCLK/TCK_63") (pintype "bidirectional"))
    )
    (net (code "64") (name "/TDI") (class "Default")
      (node (ref "U2") (pin "74") (pinfunction "PB4/TDI/TWD1_74") (pintype "bidirectional"))
    )
    (net (code "65") (name "/TDO") (class "Default")
      (node (ref "U2") (pin "77") (pinfunction "PB5/TDO/TWCK1_77") (pintype "bidirectional"))
    )
    (net (code "66") (name "/TMS{slash}SWDIO") (class "Default")
      (node (ref "TP1") (pin "2") (pinfunction "TMS_2") (pintype "bidirectional"))
      (node (ref "U2") (pin "57") (pinfunction "PB6/SWDIO/TMS_57") (pintype "bidirectional"))
    )
    (net (code "67") (name "/VDDCORE") (class "Default")
      (node (ref "C10") (pin "2") (pinfunction "2_2") (pintype "passive"))
      (node (ref "C11") (pin "2") (pinfunction "2_2") (pintype "passive"))
      (node (ref "C12") (pin "2") (pinfunction "2_2") (pintype "passive"))
      (node (ref "C7") (pin "2") (pinfunction "2_2") (pintype "passive"))
      (node (ref "C8") (pin "2") (pinfunction "2_2") (pintype "passive"))
      (node (ref "C9") (pin "2") (pinfunction "2_2") (pintype "passive"))
      (node (ref "U2") (pin "18") (pinfunction "VDDCORE1_18") (pintype "bidirectional"))
      (node (ref "U2") (pin "22") (pinfunction "VDDCORE2_22") (pintype "bidirectional"))
      (node (ref "U2") (pin "39") (pinfunction "VDDCORE3_39") (pintype "bidirectional"))
      (node (ref "U2") (pin "4") (pinfunction "VDDOUT_4") (pintype "bidirectional"))
      (node (ref "U2") (pin "76") (pinfunction "VDDCORE4_76") (pintype "bidirectional"))
      (node (ref "U2") (pin "86") (pinfunction "VDDPLL_86") (pintype "bidirectional"))
      (node (ref "U2") (pin "96") (pinfunction "VDDUTMIC_96") (pintype "bidirectional"))
    )
    (net (code "68") (name "GND") (class "Default")
      (node (ref "C1") (pin "2") (pinfunction "2_2") (pintype "passive"))
      (node (ref "C10") (pin "1") (pinfunction "1_1") (pintype "passive"))
      (node (ref "C11") (pin "1") (pinfunction "1_1") (pintype "passive"))
      (node (ref "C12") (pin "1") (pinfunction "1_1") (pintype "passive"))
      (node (ref "C13") (pin "1") (pinfunction "1_1") (pintype "passive"))
      (node (ref "C14") (pin "2") (pinfunction "2_2") (pintype "passive"))
      (node (ref "C15") (pin "1") (pinfunction "1_1") (pintype "passive"))
      (node (ref "C16") (pin "2") (pinfunction "2_2") (pintype "passive"))
      (node (ref "C17") (pin "2") (pinfunction "2_2") (pintype "passive"))
      (node (ref "C18") (pin "1") (pinfunction "1_1") (pintype "passive"))
      (node (ref "C19") (pin "2") (pinfunction "2_2") (pintype "passive"))
      (node (ref "C2") (pin "1") (pinfunction "1_1") (pintype "passive"))
      (node (ref "C20") (pin "2") (pinfunction "2_2") (pintype "passive"))
      (node (ref "C21") (pin "2") (pinfunction "2_2") (pintype "passive"))
      (node (ref "C22") (pin "2") (pinfunction "2_2") (pintype "passive"))
      (node (ref "C23") (pin "2") (pinfunction "2_2") (pintype "passive"))
      (node (ref "C24") (pin "1") (pinfunction "1_1") (pintype "passive"))
      (node (ref "C25") (pin "2") (pinfunction "2_2") (pintype "passive"))
      (node (ref "C26") (pin "2") (pinfunction "2_2") (pintype "passive"))
      (node (ref "C27") (pin "2") (pinfunction "2_2") (pintype "passive"))
      (node (ref "C28") (pin "2") (pinfunction "2_2") (pintype "passive"))
      (node (ref "C29") (pin "1") (pinfunction "1_1") (pintype "passive"))
      (node (ref "C3") (pin "1") (pinfunction "1_1") (pintype "passive"))
      (node (ref "C30") (pin "2") (pinfunction "2_2") (pintype "passive"))
      (node (ref "C31") (pin "2") (pinfunction "2_2") (pintype "passive"))
      (node (ref "C4") (pin "1") (pinfunction "1_1") (pintype "passive"))
      (node (ref "C5") (pin "1") (pinfunction "1_1") (pintype "passive"))
      (node (ref "C6") (pin "1") (pinfunction "1_1") (pintype "passive"))
      (node (ref "C7") (pin "1") (pinfunction "1_1") (pintype "passive"))
      (node (ref "C8") (pin "1") (pinfunction "1_1") (pintype "passive"))
      (node (ref "C9") (pin "1") (pinfunction "1_1") (pintype "passive"))
      (node (ref "J1") (pin "1") (pinfunction "1_1") (pintype "passive"))
      (node (ref "J1") (pin "8") (pinfunction "8_8") (pintype "passive"))
      (node (ref "J2") (pin "1") (pinfunction "1_1") (pintype "passive"))
      (node (ref "J2") (pin "8") (pinfunction "8_8") (pintype "passive"))
      (node (ref "J3") (pin "1") (pinfunction "1_1") (pintype "passive"))
      (node (ref "J3") (pin "8") (pinfunction "8_8") (pintype "passive"))
      (node (ref "J4") (pin "1") (pinfunction "1_1") (pintype "passive"))
      (node (ref "J4") (pin "8") (pinfunction "8_8") (pintype "passive"))
      (node (ref "J5") (pin "1") (pinfunction "1_1") (pintype "passive"))
      (node (ref "J5") (pin "3") (pinfunction "3_3") (pintype "passive"))
      (node (ref "J5") (pin "5") (pinfunction "5_5") (pintype "passive"))
      (node (ref "R3") (pin "1") (pinfunction "1_1") (pintype "passive"))
      (node (ref "R6") (pin "1") (pinfunction "1_1") (pintype "passive"))
      (node (ref "S1") (pin "1") (pinfunction "P_1") (pintype "passive"))
      (node (ref "S1") (pin "2") (pinfunction "P1_2") (pintype "passive"))
      (node (ref "S2") (pin "1") (pinfunction "P_1") (pintype "passive"))
      (node (ref "S2") (pin "2") (pinfunction "P1_2") (pintype "passive"))
      (node (ref "TP1") (pin "3") (pinfunction "GND_3") (pintype "bidirectional"))
      (node (ref "TP1") (pin "5") (pinfunction "NC_5") (pintype "bidirectional"))
      (node (ref "TP1") (pin "9") (pinfunction "~{TRST}_9") (pintype "bidirectional"))
      (node (ref "U1") (pin "1") (pinfunction "GND_1") (pintype "bidirectional"))
      (node (ref "U2") (pin "10") (pinfunction "GND4_10") (pintype "bidirectional"))
      (node (ref "U2") (pin "29") (pinfunction "GND5_29") (pintype "bidirectional"))
      (node (ref "U2") (pin "3") (pinfunction "GND1_3") (pintype "bidirectional"))
      (node (ref "U2") (pin "6") (pinfunction "VREFN_6") (pintype "bidirectional"))
      (node (ref "U2") (pin "67") (pinfunction "GND6_67") (pintype "bidirectional"))
      (node (ref "U2") (pin "7") (pinfunction "GND2_7") (pintype "bidirectional"))
      (node (ref "U2") (pin "8") (pinfunction "GND3_8") (pintype "bidirectional"))
      (node (ref "U3") (pin "4") (pinfunction "GND_4") (pintype "bidirectional"))
      (node (ref "U4") (pin "4") (pinfunction "GND_4") (pintype "bidirectional"))
      (node (ref "U5") (pin "4") (pinfunction "GND_4") (pintype "bidirectional"))
      (node (ref "U6") (pin "4") (pinfunction "GND_4") (pintype "bidirectional"))
      (node (ref "X1") (pin "GND") (pinfunction "GND_GND") (pintype "bidirectional"))
    )
    (net (code "69") (name "Net-(D1-CBLUE)") (class "Default")
      (node (ref "D1") (pin "B") (pinfunction "CBLUE_B") (pintype "passive"))
      (node (ref "R1") (pin "2") (pinfunction "2_2") (pintype "passive"))
    )
    (net (code "70") (name "Net-(D1-CGREEN)") (class "Default")
      (node (ref "D1") (pin "G") (pinfunction "CGREEN_G") (pintype "passive"))
      (node (ref "R3") (pin "2") (pinfunction "2_2") (pintype "passive"))
    )
    (net (code "71") (name "Net-(D1-CRED)") (class "Default")
      (node (ref "D1") (pin "R") (pinfunction "CRED_R") (pintype "passive"))
      (node (ref "R2") (pin "2") (pinfunction "2_2") (pintype "passive"))
    )
    (net (code "72") (name "Net-(D2-CBLUE)") (class "Default")
      (node (ref "D2") (pin "B") (pinfunction "CBLUE_B") (pintype "passive"))
      (node (ref "R7") (pin "2") (pinfunction "2_2") (pintype "passive"))
    )
    (net (code "73") (name "Net-(D2-CGREEN)") (class "Default")
      (node (ref "D2") (pin "G") (pinfunction "CGREEN_G") (pintype "passive"))
      (node (ref "R12") (pin "2") (pinfunction "2_2") (pintype "passive"))
    )
    (net (code "74") (name "Net-(D2-CRED)") (class "Default")
      (node (ref "D2") (pin "R") (pinfunction "CRED_R") (pintype "passive"))
      (node (ref "R11") (pin "2") (pinfunction "2_2") (pintype "passive"))
    )
    (net (code "75") (name "Net-(D3-CBLUE)") (class "Default")
      (node (ref "D3") (pin "B") (pinfunction "CBLUE_B") (pintype "passive"))
      (node (ref "R8") (pin "2") (pinfunction "2_2") (pintype "passive"))
    )
    (net (code "76") (name "Net-(D3-CGREEN)") (class "Default")
      (node (ref "D3") (pin "G") (pinfunction "CGREEN_G") (pintype "passive"))
      (node (ref "R14") (pin "2") (pinfunction "2_2") (pintype "passive"))
    )
    (net (code "77") (name "Net-(D3-CRED)") (class "Default")
      (node (ref "D3") (pin "R") (pinfunction "CRED_R") (pintype "passive"))
      (node (ref "R13") (pin "2") (pinfunction "2_2") (pintype "passive"))
    )
    (net (code "78") (name "Net-(D4-CBLUE)") (class "Default")
      (node (ref "D4") (pin "B") (pinfunction "CBLUE_B") (pintype "passive"))
      (node (ref "R9") (pin "2") (pinfunction "2_2") (pintype "passive"))
    )
    (net (code "79") (name "Net-(D4-CGREEN)") (class "Default")
      (node (ref "D4") (pin "G") (pinfunction "CGREEN_G") (pintype "passive"))
      (node (ref "R16") (pin "2") (pinfunction "2_2") (pintype "passive"))
    )
    (net (code "80") (name "Net-(D4-CRED)") (class "Default")
      (node (ref "D4") (pin "R") (pinfunction "CRED_R") (pintype "passive"))
      (node (ref "R15") (pin "2") (pinfunction "2_2") (pintype "passive"))
    )
    (net (code "81") (name "Net-(D5-CBLUE)") (class "Default")
      (node (ref "D5") (pin "B") (pinfunction "CBLUE_B") (pintype "passive"))
      (node (ref "R10") (pin "2") (pinfunction "2_2") (pintype "passive"))
    )
    (net (code "82") (name "Net-(D5-CGREEN)") (class "Default")
      (node (ref "D5") (pin "G") (pinfunction "CGREEN_G") (pintype "passive"))
      (node (ref "R18") (pin "2") (pinfunction "2_2") (pintype "passive"))
    )
    (net (code "83") (name "Net-(D5-CRED)") (class "Default")
      (node (ref "D5") (pin "R") (pinfunction "CRED_R") (pintype "passive"))
      (node (ref "R17") (pin "2") (pinfunction "2_2") (pintype "passive"))
    )
    (net (code "84") (name "Net-(L1-Pad1)") (class "Default")
      (node (ref "L1") (pin "1") (pinfunction "1_1") (pintype "passive"))
      (node (ref "R5") (pin "2") (pinfunction "2_2") (pintype "passive"))
    )
    (net (code "85") (name "Net-(L2-Pad1)") (class "Default")
      (node (ref "L2") (pin "1") (pinfunction "1_1") (pintype "passive"))
      (node (ref "R4") (pin "2") (pinfunction "2_2") (pintype "passive"))
    )
    (net (code "86") (name "Net-(Q1-2)") (class "Default")
      (node (ref "C13") (pin "2") (pinfunction "2_2") (pintype "passive"))
      (node (ref "Q1") (pin "3") (pinfunction "2_3") (pintype "passive"))
      (node (ref "U2") (pin "99") (pinfunction "PB9/XIN_99") (pintype "bidirectional"))
    )
    (net (code "87") (name "Net-(U$3-Pad1)") (class "Default")
      (node (ref "U$3") (pin "1") (pinfunction "1_1") (pintype "passive"))
      (node (ref "X1") (pin "D+") (pinfunction "D+_D+") (pintype "bidirectional"))
    )
    (net (code "88") (name "Net-(U$4-Pad1)") (class "Default")
      (node (ref "U$4") (pin "1") (pinfunction "1_1") (pintype "passive"))
      (node (ref "X1") (pin "D-") (pinfunction "D-_D-") (pintype "bidirectional"))
    )
    (net (code "89") (name "Net-(U2-PB8{slash}XOUT)") (class "Default")
      (node (ref "C14") (pin "1") (pinfunction "1_1") (pintype "passive"))
      (node (ref "Q1") (pin "1") (pinfunction "1_1") (pintype "passive"))
      (node (ref "U2") (pin "98") (pinfunction "PB8/XOUT_98") (pintype "bidirectional"))
    )
    (net (code "90") (name "Net-(U2-VBG)") (class "Default")
      (node (ref "C16") (pin "1") (pinfunction "1_1") (pintype "passive"))
      (node (ref "R6") (pin "2") (pinfunction "2_2") (pintype "passive"))
      (node (ref "U2") (pin "97") (pinfunction "VBG_97") (pintype "bidirectional"))
    )
    (net (code "91") (name "Net-(U2-VDDPLLUSB)") (class "Default")
      (node (ref "C18") (pin "2") (pinfunction "2_2") (pintype "passive"))
      (node (ref "L2") (pin "2") (pinfunction "2_2") (pintype "passive"))
      (node (ref "U2") (pin "90") (pinfunction "VDDPLLUSB_90") (pintype "bidirectional"))
    )
    (net (code "92") (name "Net-(U2-VREFP)") (class "Default")
      (node (ref "C17") (pin "1") (pinfunction "1_1") (pintype "passive"))
      (node (ref "L1") (pin "2") (pinfunction "2_2") (pintype "passive"))
      (node (ref "U2") (pin "9") (pinfunction "VREFP_9") (pintype "bidirectional"))
    )
    (net (code "93") (name "Net-(U3-A)") (class "Default")
      (node (ref "J1") (pin "3") (pinfunction "3_3") (pintype "passive"))
      (node (ref "U3") (pin "8") (pinfunction "A_8") (pintype "bidirectional"))
    )
    (net (code "94") (name "Net-(U3-B)") (class "Default")
      (node (ref "J1") (pin "4") (pinfunction "4_4") (pintype "passive"))
      (node (ref "U3") (pin "7") (pinfunction "B_7") (pintype "bidirectional"))
    )
    (net (code "95") (name "Net-(U3-Y)") (class "Default")
      (node (ref "J1") (pin "6") (pinfunction "6_6") (pintype "passive"))
      (node (ref "U3") (pin "5") (pinfunction "Y_5") (pintype "bidirectional"))
    )
    (net (code "96") (name "Net-(U3-Z)") (class "Default")
      (node (ref "J1") (pin "5") (pinfunction "5_5") (pintype "passive"))
      (node (ref "U3") (pin "6") (pinfunction "Z_6") (pintype "bidirectional"))
    )
    (net (code "97") (name "Net-(U4-A)") (class "Default")
      (node (ref "J2") (pin "3") (pinfunction "3_3") (pintype "passive"))
      (node (ref "U4") (pin "8") (pinfunction "A_8") (pintype "bidirectional"))
    )
    (net (code "98") (name "Net-(U4-B)") (class "Default")
      (node (ref "J2") (pin "4") (pinfunction "4_4") (pintype "passive"))
      (node (ref "U4") (pin "7") (pinfunction "B_7") (pintype "bidirectional"))
    )
    (net (code "99") (name "Net-(U4-Y)") (class "Default")
      (node (ref "J2") (pin "6") (pinfunction "6_6") (pintype "passive"))
      (node (ref "U4") (pin "5") (pinfunction "Y_5") (pintype "bidirectional"))
    )
    (net (code "100") (name "Net-(U4-Z)") (class "Default")
      (node (ref "J2") (pin "5") (pinfunction "5_5") (pintype "passive"))
      (node (ref "U4") (pin "6") (pinfunction "Z_6") (pintype "bidirectional"))
    )
    (net (code "101") (name "Net-(U5-A)") (class "Default")
      (node (ref "J3") (pin "3") (pinfunction "3_3") (pintype "passive"))
      (node (ref "U5") (pin "8") (pinfunction "A_8") (pintype "bidirectional"))
    )
    (net (code "102") (name "Net-(U5-B)") (class "Default")
      (node (ref "J3") (pin "4") (pinfunction "4_4") (pintype "passive"))
      (node (ref "U5") (pin "7") (pinfunction "B_7") (pintype "bidirectional"))
    )
    (net (code "103") (name "Net-(U5-Y)") (class "Default")
      (node (ref "J3") (pin "6") (pinfunction "6_6") (pintype "passive"))
      (node (ref "U5") (pin "5") (pinfunction "Y_5") (pintype "bidirectional"))
    )
    (net (code "104") (name "Net-(U5-Z)") (class "Default")
      (node (ref "J3") (pin "5") (pinfunction "5_5") (pintype "passive"))
      (node (ref "U5") (pin "6") (pinfunction "Z_6") (pintype "bidirectional"))
    )
    (net (code "105") (name "Net-(U6-A)") (class "Default")
      (node (ref "J4") (pin "3") (pinfunction "3_3") (pintype "passive"))
      (node (ref "U6") (pin "8") (pinfunction "A_8") (pintype "bidirectional"))
    )
    (net (code "106") (name "Net-(U6-B)") (class "Default")
      (node (ref "J4") (pin "4") (pinfunction "4_4") (pintype "passive"))
      (node (ref "U6") (pin "7") (pinfunction "B_7") (pintype "bidirectional"))
    )
    (net (code "107") (name "Net-(U6-Y)") (class "Default")
      (node (ref "J4") (pin "6") (pinfunction "6_6") (pintype "passive"))
      (node (ref "U6") (pin "5") (pinfunction "Y_5") (pintype "bidirectional"))
    )
    (net (code "108") (name "Net-(U6-Z)") (class "Default")
      (node (ref "J4") (pin "5") (pinfunction "5_5") (pintype "passive"))
      (node (ref "U6") (pin "6") (pinfunction "Z_6") (pintype "bidirectional"))
    )
    (net (code "109") (name "unconnected-(TP1-RTCK-Pad7)") (class "Default")
      (node (ref "TP1") (pin "7") (pinfunction "RTCK_7") (pintype "bidirectional"))
    )
    (net (code "110") (name "unconnected-(TP1-TDI-Pad8)") (class "Default")
      (node (ref "TP1") (pin "8") (pinfunction "TDI_8") (pintype "bidirectional"))
    )
    (net (code "111") (name "unconnected-(TP1-TDO-Pad6)") (class "Default")
      (node (ref "TP1") (pin "6") (pinfunction "TDO_6") (pintype "bidirectional"))
    )
    (net (code "112") (name "unconnected-(U2-JTAGSEL-Pad73)") (class "Default")
      (node (ref "U2") (pin "73") (pinfunction "JTAGSEL_73") (pintype "bidirectional"))
    )
    (net (code "113") (name "unconnected-(U2-PA2-Pad66)") (class "Default")
      (node (ref "U2") (pin "66") (pinfunction "PA2_66") (pintype "bidirectional"))
    )
    (net (code "114") (name "unconnected-(U2-PA3{slash}TWD0-Pad64)") (class "Default")
      (node (ref "U2") (pin "64") (pinfunction "PA3/TWD0_64") (pintype "bidirectional"))
    )
    (net (code "115") (name "unconnected-(U2-PA7{slash}XIN32-Pad24)") (class "Default")
      (node (ref "U2") (pin "24") (pinfunction "PA7/XIN32_24") (pintype "bidirectional"))
    )
    (net (code "116") (name "unconnected-(U2-PA12{slash}PWMC0_PWMH1-Pad48)") (class "Default")
      (node (ref "U2") (pin "48") (pinfunction "PA12/PWMC0_PWMH1_48") (pintype "bidirectional"))
    )
    (net (code "117") (name "unconnected-(U2-PA14{slash}WMC0_PWMH3-Pad34)") (class "Default")
      (node (ref "U2") (pin "34") (pinfunction "PA14/WMC0_PWMH3_34") (pintype "bidirectional"))
    )
    (net (code "118") (name "unconnected-(U2-PA24-Pad38)") (class "Default")
      (node (ref "U2") (pin "38") (pinfunction "PA24_38") (pintype "bidirectional"))
    )
    (net (code "119") (name "unconnected-(U2-PA25-Pad40)") (class "Default")
      (node (ref "U2") (pin "40") (pinfunction "PA25_40") (pintype "bidirectional"))
    )
    (net (code "120") (name "unconnected-(U2-PA26-Pad42)") (class "Default")
      (node (ref "U2") (pin "42") (pinfunction "PA26_42") (pintype "bidirectional"))
    )
    (net (code "121") (name "unconnected-(U2-PB12{slash}ERASE-Pad61)") (class "Default")
      (node (ref "U2") (pin "61") (pinfunction "PB12/ERASE_61") (pintype "bidirectional"))
    )
    (net (code "122") (name "unconnected-(U2-PD16-Pad56)") (class "Default")
      (node (ref "U2") (pin "56") (pinfunction "PD16_56") (pintype "bidirectional"))
    )
    (net (code "123") (name "unconnected-(U2-PD17-Pad53)") (class "Default")
      (node (ref "U2") (pin "53") (pinfunction "PD17_53") (pintype "bidirectional"))
    )
    (net (code "124") (name "unconnected-(U2-PD24-Pad37)") (class "Default")
      (node (ref "U2") (pin "37") (pinfunction "PD24_37") (pintype "bidirectional"))
    )
    (net (code "125") (name "unconnected-(U2-PD31-Pad2)") (class "Default")
      (node (ref "U2") (pin "2") (pinfunction "PD31_2") (pintype "bidirectional"))
    )
    (net (code "126") (name "unconnected-(U2-TST-Pad60)") (class "Default")
      (node (ref "U2") (pin "60") (pinfunction "TST_60") (pintype "bidirectional"))
    )
  )
)
